# opaq_n1.net
KiCad netlist of a schematic drawn in EAGLE
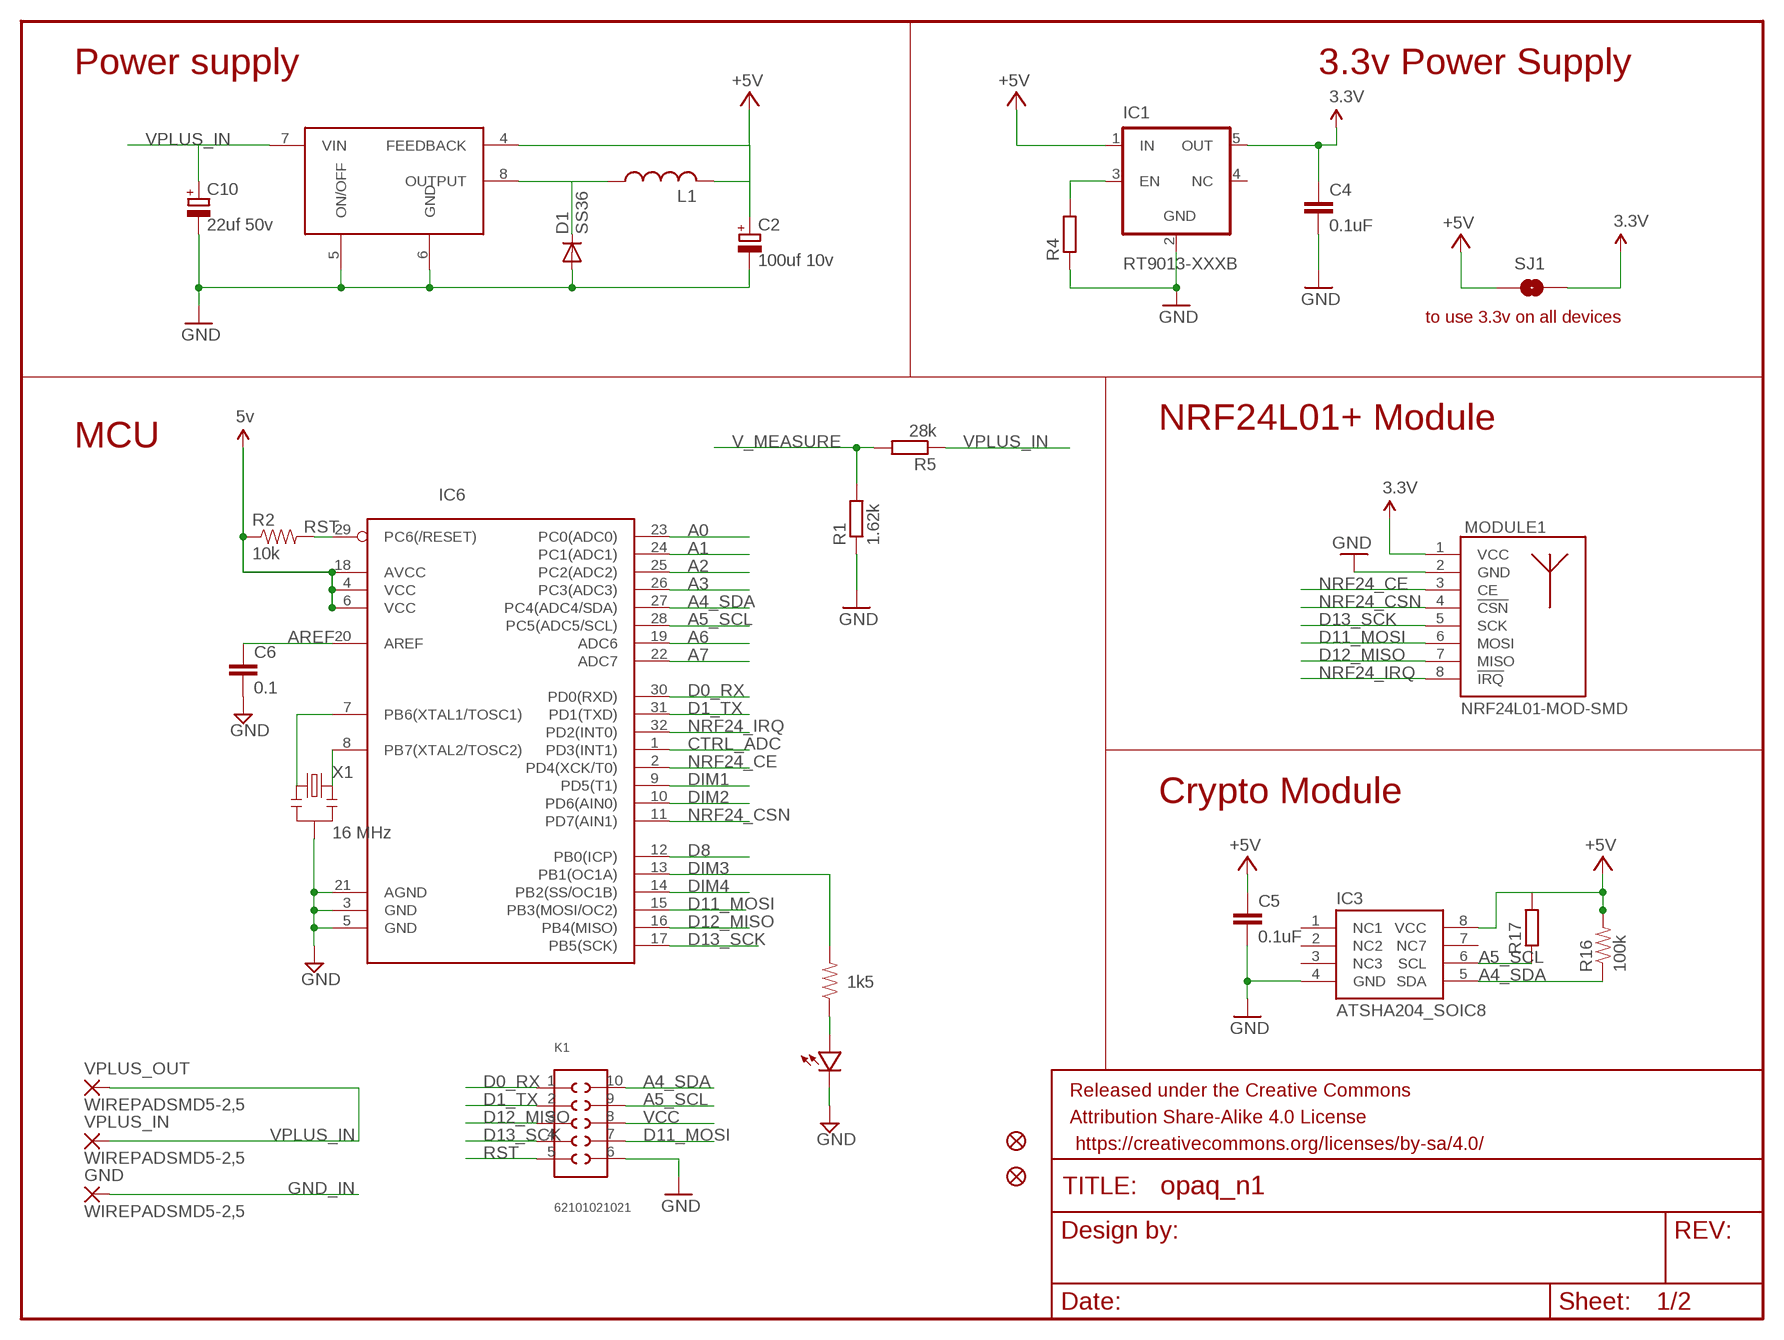
[diagram p0: schematic, sheet 1]
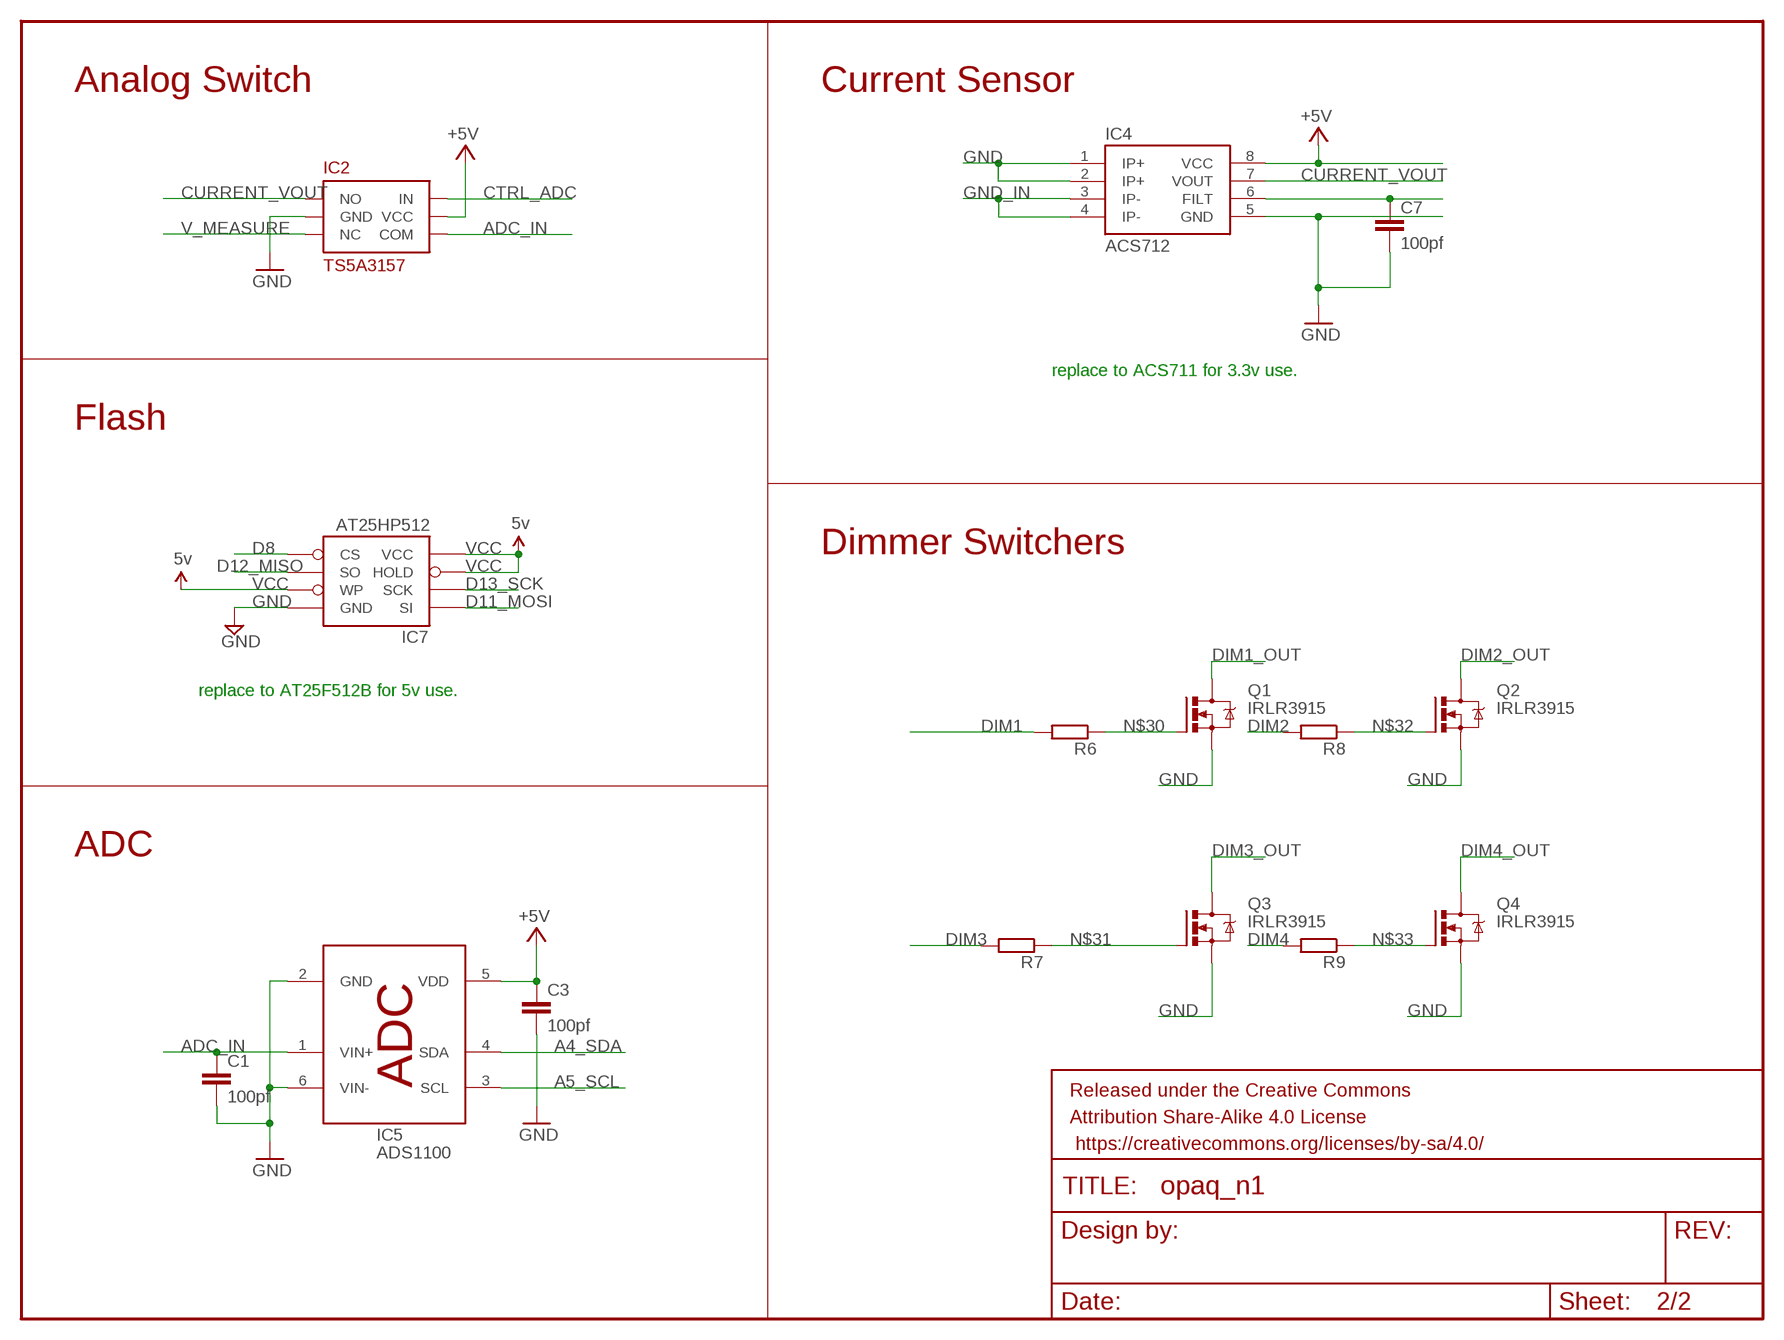
[diagram p1: schematic, sheet 2]

(export (version "E")
  (design (tool "Eeschema 10.0.6"))
  (components
    (comp (ref "C1")
      (value "100pf")
      (footprint "eagle-import:0402-CAP")
      (libsource (lib "eagle-import") (part "SparkFun-Passives_CAP0402-CAP"))
    )
    (comp (ref "C3")
      (value "100pf")
      (footprint "eagle-import:0402-CAP")
      (libsource (lib "eagle-import") (part "SparkFun-Passives_CAP0402-CAP"))
    )
    (comp (ref "C7")
      (value "100pf")
      (footprint "eagle-import:0402-CAP")
      (libsource (lib "eagle-import") (part "SparkFun-Passives_CAP0402-CAP"))
    )
    (comp (ref "FRAME2")
      (value "FRAME-LETTERNO_PACKAGE")
      (footprint "eagle-import:DUMMY")
      (fields (field (name "DESIGNER") "Nobody"))
      (libsource (lib "eagle-import") (part "FRAME-LETTERNO_PACKAGE"))
    )
    (comp (ref "IC2")
      (value "TS5A3157")
      (footprint "eagle-import:SOT23-6")
      (libsource (lib "eagle-import") (part "TS5A3157"))
    )
    (comp (ref "IC4")
      (value "ACS712")
      (footprint "eagle-import:SO08")
      (libsource (lib "eagle-import") (part "ACS712"))
    )
    (comp (ref "IC5")
      (value "ADS1100")
      (footprint "eagle-import:SOT23-6")
      (fields (field (name "MF") "TI"))
      (libsource (lib "eagle-import") (part "ADS1100"))
    )
    (comp (ref "IC7")
      (value "AT25HP512")
      (footprint "eagle-import:SO08WIDE")
      (libsource (lib "eagle-import") (part "AT25F512BWIDE_5.3MM"))
    )
    (comp (ref "Q1")
      (value "IRLR3915")
      (footprint "eagle-import:D-PAK_TO252AA")
      (libsource (lib "eagle-import") (part "IRLR3915"))
    )
    (comp (ref "Q2")
      (value "IRLR3915")
      (footprint "eagle-import:D-PAK_TO252AA")
      (libsource (lib "eagle-import") (part "IRLR3915"))
    )
    (comp (ref "Q3")
      (value "IRLR3915")
      (footprint "eagle-import:D-PAK_TO252AA")
      (libsource (lib "eagle-import") (part "IRLR3915"))
    )
    (comp (ref "Q4")
      (value "IRLR3915")
      (footprint "eagle-import:D-PAK_TO252AA")
      (libsource (lib "eagle-import") (part "IRLR3915"))
    )
    (comp (ref "R6")
      (value "R-EU_R0805")
      (footprint "eagle-import:0805")
      (libsource (lib "eagle-import") (part "R-EU_R0805"))
    )
    (comp (ref "R7")
      (value "R-EU_R0805")
      (footprint "eagle-import:0805")
      (libsource (lib "eagle-import") (part "R-EU_R0805"))
    )
    (comp (ref "R8")
      (value "R-EU_R0805")
      (footprint "eagle-import:0805")
      (libsource (lib "eagle-import") (part "R-EU_R0805"))
    )
    (comp (ref "R9")
      (value "R-EU_R0805")
      (footprint "eagle-import:0805")
      (libsource (lib "eagle-import") (part "R-EU_R0805"))
    )
    (comp (ref "C2")
      (value "100uf 10v")
      (footprint "eagle-import:C_6032-28R")
      (libsource (lib "eagle-import") (part "CPOL-EUC/6032-28R"))
    )
    (comp (ref "C4")
      (value "0.1uF")
      (footprint "eagle-import:0805")
      (libsource (lib "eagle-import") (part "SparkFun-Passives_CAP0805"))
    )
    (comp (ref "C5")
      (value "0.1uF")
      (footprint "eagle-import:0805")
      (libsource (lib "eagle-import") (part "SparkFun-Passives_CAP0805"))
    )
    (comp (ref "C6")
      (value "0.1")
      (footprint "eagle-import:0603-CAP")
      (libsource (lib "eagle-import") (part "CAP0603-CAP"))
    )
    (comp (ref "C10")
      (value "22uf 50v")
      (footprint "eagle-import:D_7343-31R")
      (libsource (lib "eagle-import") (part "CPOL-EUD/7343-31R"))
    )
    (comp (ref "D1")
      (value "SS36")
      (footprint "eagle-import:SMA-DIODE")
      (libsource (lib "eagle-import") (part "DIODESMA"))
    )
    (comp (ref "DIM")
      (value "LED0603")
      (footprint "eagle-import:0603-LED")
      (libsource (lib "eagle-import") (part "LED0603"))
    )
    (comp (ref "FRAME1")
      (value "FRAME-LETTER")
      (footprint "eagle-import:CREATIVE_COMMONS")
      (libsource (lib "eagle-import") (part "FRAME-LETTER"))
    )
    (comp (ref "GND")
      (value "WIREPADSMD5-2,5")
      (footprint "eagle-import:5-2,5")
      (libsource (lib "eagle-import") (part "WIREPADSMD5-2,5"))
    )
    (comp (ref "IC1")
      (value "RT9013-XXXB")
      (footprint "eagle-import:SOT23-5")
      (libsource (lib "eagle-import") (part "RT9013-XXXB"))
    )
    (comp (ref "IC3")
      (value "ATSHA204_SOIC8")
      (footprint "eagle-import:SOIC8")
      (libsource (lib "eagle-import") (part "ATSHA204_SOIC8"))
    )
    (comp (ref "IC6")
      (value "ATMega-328")
      (footprint "eagle-import:MLF32")
      (libsource (lib "eagle-import") (part "ATMEGA168/328MLF"))
    )
    (comp (ref "IC8")
      (value "LM2594HV")
      (footprint "eagle-import:SO08")
      (libsource (lib "eagle-import") (part "LM2594"))
    )
    (comp (ref "JP1")
      (value "FIDUCIAL1X2.5")
      (footprint "eagle-import:FIDUCIAL-1X2.5")
      (libsource (lib "eagle-import") (part "FIDUCIAL1X2.5"))
    )
    (comp (ref "JP2")
      (value "FIDUCIAL1X2.5")
      (footprint "eagle-import:FIDUCIAL-1X2.5")
      (libsource (lib "eagle-import") (part "FIDUCIAL1X2.5"))
    )
    (comp (ref "K1")
      (value "62101021021")
      (footprint "eagle-import:62101021021")
      (libsource (lib "eagle-import") (part "62101021021"))
    )
    (comp (ref "L1")
      (value "NR6045")
      (footprint "eagle-import:2525")
      (libsource (lib "eagle-import") (part "NR6045"))
    )
    (comp (ref "MODULE1")
      (value "NRF24L01-MOD-SMD")
      (footprint "eagle-import:SMD8-MODULE")
      (libsource (lib "eagle-import") (part "NRF24L01-MOD-SMD"))
    )
    (comp (ref "R1")
      (value "1.62k")
      (footprint "eagle-import:0805")
      (libsource (lib "eagle-import") (part "R-EU_R0805"))
    )
    (comp (ref "R2")
      (value "10k")
      (footprint "eagle-import:0603-RES")
      (libsource (lib "eagle-import") (part "RESISTOR0603-RES"))
    )
    (comp (ref "R3")
      (value "1k5")
      (footprint "eagle-import:0603-RES")
      (libsource (lib "eagle-import") (part "RESISTOR0603-RES"))
    )
    (comp (ref "R4")
      (value "R-EU_R0805")
      (footprint "eagle-import:0805")
      (libsource (lib "eagle-import") (part "R-EU_R0805"))
    )
    (comp (ref "R5")
      (value "28k")
      (footprint "eagle-import:0805")
      (libsource (lib "eagle-import") (part "R-EU_R0805"))
    )
    (comp (ref "R16")
      (value "100k")
      (footprint "eagle-import:0805")
      (libsource (lib "eagle-import") (part "SparkFun-Passives_RESISTOR0805-RES"))
    )
    (comp (ref "R17")
      (value "R-EU_R0805")
      (footprint "eagle-import:0805")
      (libsource (lib "eagle-import") (part "R-EU_R0805"))
    )
    (comp (ref "SJ1")
      (value "SOLDERJUMPERTRACE")
      (footprint "eagle-import:SJ_2S-TRACE")
      (libsource (lib "eagle-import") (part "SOLDERJUMPERTRACE"))
    )
    (comp (ref "VPLUS_IN")
      (value "WIREPADSMD5-2,5")
      (footprint "eagle-import:5-2,5")
      (libsource (lib "eagle-import") (part "WIREPADSMD5-2,5"))
    )
    (comp (ref "VPLUS_OUT")
      (value "WIREPADSMD5-2,5")
      (footprint "eagle-import:5-2,5")
      (libsource (lib "eagle-import") (part "WIREPADSMD5-2,5"))
    )
    (comp (ref "X1")
      (value "16 MHz")
      (footprint "eagle-import:RESONATOR-SMD")
      (libsource (lib "eagle-import") (part "RESONATORSMD"))
    )
  )
  (nets
    (net (code "1") (name "+5V") (class "Default")
      (node (ref "C2") (pin "+") (pinfunction "+_+") (pintype "passive"))
      (node (ref "C3") (pin "1") (pinfunction "1_1") (pintype "passive"))
      (node (ref "C5") (pin "1") (pinfunction "1_1") (pintype "passive"))
      (node (ref "IC1") (pin "1") (pinfunction "IN_1") (pintype "input"))
      (node (ref "IC2") (pin "5") (pinfunction "VCC_5") (pintype "bidirectional"))
      (node (ref "IC3") (pin "8") (pinfunction "VCC_8") (pintype "power_in"))
      (node (ref "IC4") (pin "8") (pinfunction "VCC_8") (pintype "bidirectional"))
      (node (ref "IC5") (pin "5") (pinfunction "VDD_5") (pintype "power_in"))
      (node (ref "IC8") (pin "4") (pinfunction "FEEDBACK_4") (pintype "bidirectional"))
      (node (ref "L1") (pin "P$1") (pinfunction "P$1_P$1") (pintype "passive"))
      (node (ref "R16") (pin "2") (pinfunction "2_2") (pintype "passive"))
      (node (ref "R17") (pin "2") (pinfunction "2_2") (pintype "passive"))
      (node (ref "SJ1") (pin "1") (pinfunction "1_1") (pintype "passive"))
    )
    (net (code "2") (name "3.3V") (class "Default")
      (node (ref "C4") (pin "1") (pinfunction "1_1") (pintype "passive"))
      (node (ref "IC1") (pin "5") (pinfunction "OUT_5") (pintype "passive"))
      (node (ref "MODULE1") (pin "1") (pinfunction "VCC_1") (pintype "power_in"))
      (node (ref "SJ1") (pin "2") (pinfunction "2_2") (pintype "passive"))
    )
    (net (code "3") (name "A0") (class "Default")
      (node (ref "IC6") (pin "23") (pinfunction "PC0(ADC0)_23") (pintype "bidirectional"))
    )
    (net (code "4") (name "A1") (class "Default")
      (node (ref "IC6") (pin "24") (pinfunction "PC1(ADC1)_24") (pintype "bidirectional"))
    )
    (net (code "5") (name "A2") (class "Default")
      (node (ref "IC6") (pin "25") (pinfunction "PC2(ADC2)_25") (pintype "bidirectional"))
    )
    (net (code "6") (name "A3") (class "Default")
      (node (ref "IC6") (pin "26") (pinfunction "PC3(ADC3)_26") (pintype "bidirectional"))
    )
    (net (code "7") (name "A4_SDA") (class "Default")
      (node (ref "IC3") (pin "5") (pinfunction "SDA_5") (pintype "bidirectional"))
      (node (ref "IC5") (pin "4") (pinfunction "SDA_4") (pintype "bidirectional"))
      (node (ref "IC6") (pin "27") (pinfunction "PC4(ADC4/SDA)_27") (pintype "bidirectional"))
      (node (ref "K1") (pin "10") (pinfunction "10_10") (pintype "passive"))
      (node (ref "R16") (pin "1") (pinfunction "1_1") (pintype "passive"))
    )
    (net (code "8") (name "A5_SCL") (class "Default")
      (node (ref "IC3") (pin "6") (pinfunction "SCL_6") (pintype "bidirectional"))
      (node (ref "IC5") (pin "3") (pinfunction "SCL_3") (pintype "input"))
      (node (ref "IC6") (pin "28") (pinfunction "PC5(ADC5/SCL)_28") (pintype "bidirectional"))
      (node (ref "K1") (pin "9") (pinfunction "9_9") (pintype "passive"))
      (node (ref "R17") (pin "1") (pinfunction "1_1") (pintype "passive"))
    )
    (net (code "9") (name "A6") (class "Default")
      (node (ref "IC6") (pin "19") (pinfunction "ADC6_19") (pintype "bidirectional"))
    )
    (net (code "10") (name "A7") (class "Default")
      (node (ref "IC6") (pin "22") (pinfunction "ADC7_22") (pintype "bidirectional"))
    )
    (net (code "11") (name "ADC_IN") (class "Default")
      (node (ref "C1") (pin "1") (pinfunction "1_1") (pintype "passive"))
      (node (ref "IC2") (pin "4") (pinfunction "COM_4") (pintype "bidirectional"))
      (node (ref "IC5") (pin "1") (pinfunction "VIN+_1") (pintype "input"))
    )
    (net (code "12") (name "AREF") (class "Default")
      (node (ref "C6") (pin "1") (pinfunction "1_1") (pintype "passive"))
      (node (ref "IC6") (pin "20") (pinfunction "AREF_20") (pintype "bidirectional"))
    )
    (net (code "13") (name "CTRL_ADC") (class "Default")
      (node (ref "IC2") (pin "6") (pinfunction "IN_6") (pintype "bidirectional"))
      (node (ref "IC6") (pin "1") (pinfunction "PD3(INT1)_1") (pintype "bidirectional"))
    )
    (net (code "14") (name "CURRENT_VOUT") (class "Default")
      (node (ref "IC2") (pin "1") (pinfunction "NO_1") (pintype "bidirectional"))
      (node (ref "IC4") (pin "7") (pinfunction "VOUT_7") (pintype "bidirectional"))
    )
    (net (code "15") (name "D0_RX") (class "Default")
      (node (ref "IC6") (pin "30") (pinfunction "PD0(RXD)_30") (pintype "bidirectional"))
      (node (ref "K1") (pin "1") (pinfunction "1_1") (pintype "passive"))
    )
    (net (code "16") (name "D1_TX") (class "Default")
      (node (ref "IC6") (pin "31") (pinfunction "PD1(TXD)_31") (pintype "bidirectional"))
      (node (ref "K1") (pin "2") (pinfunction "2_2") (pintype "passive"))
    )
    (net (code "17") (name "D8") (class "Default")
      (node (ref "IC6") (pin "12") (pinfunction "PB0(ICP)_12") (pintype "bidirectional"))
      (node (ref "IC7") (pin "1") (pinfunction "CS_1") (pintype "bidirectional"))
    )
    (net (code "18") (name "D11_MOSI") (class "Default")
      (node (ref "IC6") (pin "15") (pinfunction "PB3(MOSI/OC2)_15") (pintype "bidirectional"))
      (node (ref "IC7") (pin "5") (pinfunction "SI_5") (pintype "bidirectional"))
      (node (ref "K1") (pin "7") (pinfunction "7_7") (pintype "passive"))
      (node (ref "MODULE1") (pin "6") (pinfunction "MOSI_6") (pintype "input"))
    )
    (net (code "19") (name "D12_MISO") (class "Default")
      (node (ref "IC6") (pin "16") (pinfunction "PB4(MISO)_16") (pintype "bidirectional"))
      (node (ref "IC7") (pin "2") (pinfunction "SO_2") (pintype "bidirectional"))
      (node (ref "K1") (pin "3") (pinfunction "3_3") (pintype "passive"))
      (node (ref "MODULE1") (pin "7") (pinfunction "MISO_7") (pintype "output"))
    )
    (net (code "20") (name "D13_SCK") (class "Default")
      (node (ref "IC6") (pin "17") (pinfunction "PB5(SCK)_17") (pintype "bidirectional"))
      (node (ref "IC7") (pin "6") (pinfunction "SCK_6") (pintype "bidirectional"))
      (node (ref "K1") (pin "4") (pinfunction "4_4") (pintype "passive"))
      (node (ref "MODULE1") (pin "5") (pinfunction "SCK_5") (pintype "input"))
    )
    (net (code "21") (name "DIM1") (class "Default")
      (node (ref "IC6") (pin "9") (pinfunction "PD5(T1)_9") (pintype "bidirectional"))
      (node (ref "R6") (pin "2") (pinfunction "2_2") (pintype "passive"))
    )
    (net (code "22") (name "DIM1_OUT") (class "Default")
      (node (ref "Q1") (pin "4") (pinfunction "D_4") (pintype "passive"))
    )
    (net (code "23") (name "DIM2") (class "Default")
      (node (ref "IC6") (pin "10") (pinfunction "PD6(AIN0)_10") (pintype "bidirectional"))
      (node (ref "R8") (pin "2") (pinfunction "2_2") (pintype "passive"))
    )
    (net (code "24") (name "DIM2_OUT") (class "Default")
      (node (ref "Q2") (pin "4") (pinfunction "D_4") (pintype "passive"))
    )
    (net (code "25") (name "DIM3") (class "Default")
      (node (ref "IC6") (pin "13") (pinfunction "PB1(OC1A)_13") (pintype "bidirectional"))
      (node (ref "R3") (pin "2") (pinfunction "2_2") (pintype "passive"))
      (node (ref "R7") (pin "2") (pinfunction "2_2") (pintype "passive"))
    )
    (net (code "26") (name "DIM3_OUT") (class "Default")
      (node (ref "Q3") (pin "4") (pinfunction "D_4") (pintype "passive"))
    )
    (net (code "27") (name "DIM4") (class "Default")
      (node (ref "IC6") (pin "14") (pinfunction "PB2(SS/OC1B)_14") (pintype "bidirectional"))
      (node (ref "R9") (pin "2") (pinfunction "2_2") (pintype "passive"))
    )
    (net (code "28") (name "DIM4_OUT") (class "Default")
      (node (ref "Q4") (pin "4") (pinfunction "D_4") (pintype "passive"))
    )
    (net (code "29") (name "GND") (class "Default")
      (node (ref "C1") (pin "2") (pinfunction "2_2") (pintype "passive"))
      (node (ref "C10") (pin "-") (pinfunction "-_-") (pintype "passive"))
      (node (ref "C2") (pin "-") (pinfunction "-_-") (pintype "passive"))
      (node (ref "C3") (pin "2") (pinfunction "2_2") (pintype "passive"))
      (node (ref "C4") (pin "2") (pinfunction "2_2") (pintype "passive"))
      (node (ref "C5") (pin "2") (pinfunction "2_2") (pintype "passive"))
      (node (ref "C6") (pin "2") (pinfunction "2_2") (pintype "passive"))
      (node (ref "C7") (pin "2") (pinfunction "2_2") (pintype "passive"))
      (node (ref "D1") (pin "A") (pinfunction "A_A") (pintype "passive"))
      (node (ref "DIM") (pin "MINUS") (pinfunction "MINUS_MINUS") (pintype "passive"))
      (node (ref "IC1") (pin "2") (pinfunction "GND_2") (pintype "power_in"))
      (node (ref "IC2") (pin "2") (pinfunction "GND_2") (pintype "bidirectional"))
      (node (ref "IC3") (pin "4") (pinfunction "GND_4") (pintype "power_in"))
      (node (ref "IC4") (pin "1") (pinfunction "IP+_1") (pintype "bidirectional"))
      (node (ref "IC4") (pin "2") (pinfunction "IP+_2") (pintype "bidirectional"))
      (node (ref "IC4") (pin "5") (pinfunction "GND_5") (pintype "bidirectional"))
      (node (ref "IC5") (pin "2") (pinfunction "GND_2") (pintype "power_in"))
      (node (ref "IC5") (pin "6") (pinfunction "VIN-_6") (pintype "input"))
      (node (ref "IC6") (pin "21") (pinfunction "AGND_21") (pintype "bidirectional"))
      (node (ref "IC6") (pin "3") (pinfunction "GND_3") (pintype "bidirectional"))
      (node (ref "IC6") (pin "5") (pinfunction "GND_5") (pintype "bidirectional"))
      (node (ref "IC7") (pin "4") (pinfunction "GND_4") (pintype "bidirectional"))
      (node (ref "IC8") (pin "5") (pinfunction "ON/OFF_5") (pintype "bidirectional"))
      (node (ref "IC8") (pin "6") (pinfunction "GND_6") (pintype "bidirectional"))
      (node (ref "K1") (pin "6") (pinfunction "6_6") (pintype "passive"))
      (node (ref "MODULE1") (pin "2") (pinfunction "GND_2") (pintype "power_in"))
      (node (ref "Q1") (pin "3") (pinfunction "S_3") (pintype "passive"))
      (node (ref "Q2") (pin "3") (pinfunction "S_3") (pintype "passive"))
      (node (ref "Q3") (pin "3") (pinfunction "S_3") (pintype "passive"))
      (node (ref "Q4") (pin "3") (pinfunction "S_3") (pintype "passive"))
      (node (ref "R1") (pin "1") (pinfunction "1_1") (pintype "passive"))
      (node (ref "R4") (pin "1") (pinfunction "1_1") (pintype "passive"))
      (node (ref "X1") (pin "2") (pinfunction "2_2") (pintype "passive"))
    )
    (net (code "30") (name "GND_IN") (class "Default")
      (node (ref "GND") (pin "1") (pinfunction "P_1") (pintype "passive"))
      (node (ref "IC4") (pin "3") (pinfunction "IP-_3") (pintype "bidirectional"))
      (node (ref "IC4") (pin "4") (pinfunction "IP-_4") (pintype "bidirectional"))
    )
    (net (code "31") (name "N$30") (class "Default")
      (node (ref "Q1") (pin "1") (pinfunction "G_1") (pintype "passive"))
      (node (ref "R6") (pin "1") (pinfunction "1_1") (pintype "passive"))
    )
    (net (code "32") (name "N$31") (class "Default")
      (node (ref "Q3") (pin "1") (pinfunction "G_1") (pintype "passive"))
      (node (ref "R7") (pin "1") (pinfunction "1_1") (pintype "passive"))
    )
    (net (code "33") (name "N$32") (class "Default")
      (node (ref "Q2") (pin "1") (pinfunction "G_1") (pintype "passive"))
      (node (ref "R8") (pin "1") (pinfunction "1_1") (pintype "passive"))
    )
    (net (code "34") (name "N$33") (class "Default")
      (node (ref "Q4") (pin "1") (pinfunction "G_1") (pintype "passive"))
      (node (ref "R9") (pin "1") (pinfunction "1_1") (pintype "passive"))
    )
    (net (code "35") (name "NRF24_CE") (class "Default")
      (node (ref "IC6") (pin "2") (pinfunction "PD4(XCK/T0)_2") (pintype "bidirectional"))
      (node (ref "MODULE1") (pin "3") (pinfunction "CE_3") (pintype "input"))
    )
    (net (code "36") (name "NRF24_CSN") (class "Default")
      (node (ref "IC6") (pin "11") (pinfunction "PD7(AIN1)_11") (pintype "bidirectional"))
      (node (ref "MODULE1") (pin "4") (pinfunction "~{CSN}_4") (pintype "input"))
    )
    (net (code "37") (name "NRF24_IRQ") (class "Default")
      (node (ref "IC6") (pin "32") (pinfunction "PD2(INT0)_32") (pintype "bidirectional"))
      (node (ref "MODULE1") (pin "8") (pinfunction "~{IRQ}_8") (pintype "open_collector"))
    )
    (net (code "38") (name "Net-(DIM-PadPLUS)") (class "Default")
      (node (ref "DIM") (pin "PLUS") (pinfunction "PLUS_PLUS") (pintype "passive"))
      (node (ref "R3") (pin "1") (pinfunction "1_1") (pintype "passive"))
    )
    (net (code "39") (name "Net-(IC1-EN)") (class "Default")
      (node (ref "IC1") (pin "3") (pinfunction "EN_3") (pintype "input"))
      (node (ref "R4") (pin "2") (pinfunction "2_2") (pintype "passive"))
    )
    (net (code "40") (name "Net-(IC4-FILT)") (class "Default")
      (node (ref "C7") (pin "1") (pinfunction "1_1") (pintype "passive"))
      (node (ref "IC4") (pin "6") (pinfunction "FILT_6") (pintype "bidirectional"))
    )
    (net (code "41") (name "Net-(IC6-PB6(XTAL1{slash}TOSC1))") (class "Default")
      (node (ref "IC6") (pin "7") (pinfunction "PB6(XTAL1/TOSC1)_7") (pintype "bidirectional"))
      (node (ref "X1") (pin "1") (pinfunction "1_1") (pintype "passive"))
    )
    (net (code "42") (name "Net-(IC6-PB7(XTAL2{slash}TOSC2))") (class "Default")
      (node (ref "IC6") (pin "8") (pinfunction "PB7(XTAL2/TOSC2)_8") (pintype "bidirectional"))
      (node (ref "X1") (pin "3") (pinfunction "3_3") (pintype "passive"))
    )
    (net (code "43") (name "Net-(IC8-OUTPUT)") (class "Default")
      (node (ref "D1") (pin "C") (pinfunction "C_C") (pintype "passive"))
      (node (ref "IC8") (pin "8") (pinfunction "OUTPUT_8") (pintype "bidirectional"))
      (node (ref "L1") (pin "P$2") (pinfunction "P$2_P$2") (pintype "passive"))
    )
    (net (code "44") (name "RST") (class "Default")
      (node (ref "IC6") (pin "29") (pinfunction "PC6(/RESET)_29") (pintype "bidirectional"))
      (node (ref "K1") (pin "5") (pinfunction "5_5") (pintype "passive"))
      (node (ref "R2") (pin "2") (pinfunction "2_2") (pintype "passive"))
    )
    (net (code "45") (name "VCC") (class "Default")
      (node (ref "IC6") (pin "18") (pinfunction "AVCC_18") (pintype "bidirectional"))
      (node (ref "IC6") (pin "4") (pinfunction "VCC_4") (pintype "bidirectional"))
      (node (ref "IC6") (pin "6") (pinfunction "VCC_6") (pintype "bidirectional"))
      (node (ref "IC7") (pin "3") (pinfunction "WP_3") (pintype "bidirectional"))
      (node (ref "IC7") (pin "7") (pinfunction "HOLD_7") (pintype "bidirectional"))
      (node (ref "IC7") (pin "8") (pinfunction "VCC_8") (pintype "bidirectional"))
      (node (ref "K1") (pin "8") (pinfunction "8_8") (pintype "passive"))
      (node (ref "R2") (pin "1") (pinfunction "1_1") (pintype "passive"))
    )
    (net (code "46") (name "VPLUS_IN") (class "Default")
      (node (ref "C10") (pin "+") (pinfunction "+_+") (pintype "passive"))
      (node (ref "IC8") (pin "7") (pinfunction "VIN_7") (pintype "bidirectional"))
      (node (ref "R5") (pin "1") (pinfunction "1_1") (pintype "passive"))
      (node (ref "VPLUS_IN") (pin "1") (pinfunction "P_1") (pintype "passive"))
      (node (ref "VPLUS_OUT") (pin "1") (pinfunction "P_1") (pintype "passive"))
    )
    (net (code "47") (name "V_MEASURE") (class "Default")
      (node (ref "IC2") (pin "3") (pinfunction "NC_3") (pintype "bidirectional"))
      (node (ref "R1") (pin "2") (pinfunction "2_2") (pintype "passive"))
      (node (ref "R5") (pin "2") (pinfunction "2_2") (pintype "passive"))
    )
    (net (code "48") (name "unconnected-(IC1-NC-Pad4)") (class "Default")
      (node (ref "IC1") (pin "4") (pinfunction "NC_4") (pintype "no_connect"))
    )
    (net (code "49") (name "unconnected-(IC3-NC1-Pad1)") (class "Default")
      (node (ref "IC3") (pin "1") (pinfunction "NC1_1") (pintype "no_connect"))
    )
    (net (code "50") (name "unconnected-(IC3-NC2-Pad2)") (class "Default")
      (node (ref "IC3") (pin "2") (pinfunction "NC2_2") (pintype "no_connect"))
    )
    (net (code "51") (name "unconnected-(IC3-NC3-Pad3)") (class "Default")
      (node (ref "IC3") (pin "3") (pinfunction "NC3_3") (pintype "no_connect"))
    )
    (net (code "52") (name "unconnected-(IC3-NC7-Pad7)") (class "Default")
      (node (ref "IC3") (pin "7") (pinfunction "NC7_7") (pintype "no_connect"))
    )
  )
)
